# Radio.net
KiCad netlist of a schematic drawn in Altium Designer
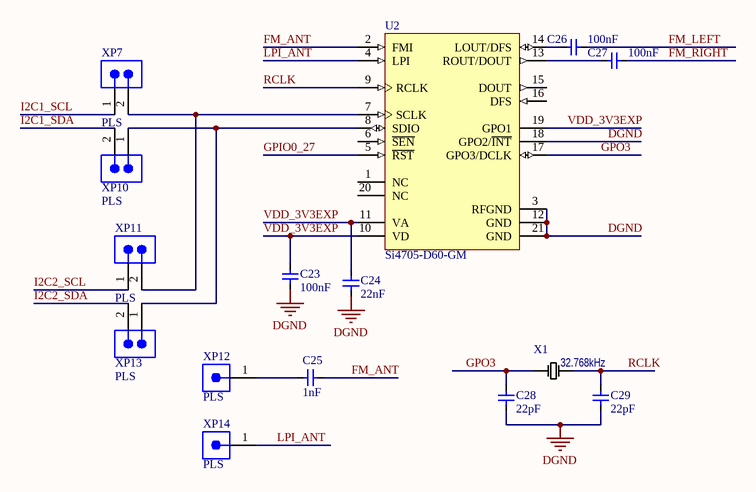
[diagram p0: Radio.SchDoc]

(export (version "E")
  (design (tool "Eeschema 10.0.6"))
  (components
    (comp (ref "C23")
      (value "100nF")
      (footprint "CAP0603R")
      (description "SMD 0805 Capacitor")
      (fields
        (field (name "PART NUMBER") "CC0603_100NF_50V_10%_X7R")
        (field (name "VOLTAGE") "50V")
        (field (name "AUTHOR") "I. Kuznetsov")
      )
      (libsource (lib "Capacitor") (part "CAP_NON_POLAR"))
    )
    (comp (ref "C24")
      (value "22nF")
      (footprint "CAP0603R")
      (description "SMD 0805 Capacitor")
      (fields
        (field (name "PART NUMBER") "CC0603_22NF_50V_10%_X7R")
        (field (name "VOLTAGE") "50V")
        (field (name "AUTHOR") "I. Kuznetsov")
      )
      (libsource (lib "Capacitor") (part "CAP_NON_POLAR"))
    )
    (comp (ref "C25")
      (value "1nF")
      (footprint "CAP0603R")
      (description "SMD 0805 Capacitor")
      (fields
        (field (name "PART NUMBER") "CC0603_1NF_50V_10%_X7R")
        (field (name "VOLTAGE") "50V")
        (field (name "AUTHOR") "I. Kuznetsov")
      )
      (libsource (lib "Capacitor") (part "CAP_NON_POLAR"))
    )
    (comp (ref "C26")
      (value "100nF")
      (footprint "CAP0603R")
      (description "SMD 0805 Capacitor")
      (fields
        (field (name "PART NUMBER") "CC0603_100NF_50V_10%_X7R")
        (field (name "VOLTAGE") "50V")
        (field (name "AUTHOR") "I. Kuznetsov")
      )
      (libsource (lib "Capacitor") (part "CAP_NON_POLAR"))
    )
    (comp (ref "C27")
      (value "100nF")
      (footprint "CAP0603R")
      (description "SMD 0805 Capacitor")
      (fields
        (field (name "PART NUMBER") "CC0603_100NF_50V_10%_X7R")
        (field (name "VOLTAGE") "50V")
        (field (name "AUTHOR") "I. Kuznetsov")
      )
      (libsource (lib "Capacitor") (part "CAP_NON_POLAR"))
    )
    (comp (ref "C28")
      (value "22pF")
      (footprint "CAP0603R")
      (description "SMD 0805 Capacitor")
      (fields
        (field (name "PART NUMBER") "CC0603_22PF_50V_5%_NP0")
        (field (name "VOLTAGE") "50V")
        (field (name "AUTHOR") "I. Kuznetsov")
      )
      (libsource (lib "Capacitor") (part "CAP_NON_POLAR"))
    )
    (comp (ref "C29")
      (value "22pF")
      (footprint "CAP0603R")
      (description "SMD 0805 Capacitor")
      (fields
        (field (name "PART NUMBER") "CC0603_22PF_50V_5%_NP0")
        (field (name "VOLTAGE") "50V")
        (field (name "AUTHOR") "I. Kuznetsov")
      )
      (libsource (lib "Capacitor") (part "CAP_NON_POLAR"))
    )
    (comp (ref "U2")
      (value "Si4705-D60-GM")
      (footprint "SLAB-QFN-20-1700x1700TP_V")
      (description "Broadcast FM Radio Receiver with RDS / RBDS, -20 to 85 degC, 20-pin QFN, Tray")
      (fields (field (name "MANUFACTURER") "Silicon Labs"))
      (libsource (lib "Altium Content Vault") (part "SLAB-Si4704_4705-QFN-20-21"))
    )
    (comp (ref "X1")
      (value "32.768kHz")
      (footprint "5020")
      (description "Кварцевый резонатор")
      (fields (field (name "PART NUMBER") "CC4V-T1A") (field (name "AUTHOR") "I. Kuznetsov"))
      (libsource (lib "Crystall") (part "2_PIN_XTAL"))
    )
    (comp (ref "XP7")
      (value "PLS")
      (footprint "PLS-02")
      (fields (field (name "PART NUMBER") "PLS-02") (field (name "MANUFACTURER") "AUK"))
      (libsource (lib "Connector") (part "CN_02P_1W"))
    )
    (comp (ref "XP10")
      (value "PLS")
      (footprint "PLS-02")
      (fields (field (name "PART NUMBER") "PLS-02") (field (name "MANUFACTURER") "AUK"))
      (libsource (lib "") (part "CN_02P_1W_1"))
    )
    (comp (ref "XP11")
      (value "PLS")
      (footprint "PLS-02")
      (fields (field (name "PART NUMBER") "PLS-02") (field (name "MANUFACTURER") "AUK"))
      (libsource (lib "Connector") (part "CN_02P_1W"))
    )
    (comp (ref "XP12")
      (value "PLS")
      (footprint "PLS-01")
      (fields (field (name "PART NUMBER") "PLS-01") (field (name "MANUFACTURER") "AUK"))
      (libsource (lib "Connector") (part "CN_01P_1W"))
    )
    (comp (ref "XP13")
      (value "PLS")
      (footprint "PLS-02")
      (fields (field (name "PART NUMBER") "PLS-02") (field (name "MANUFACTURER") "AUK"))
      (libsource (lib "") (part "CN_02P_1W_1"))
    )
    (comp (ref "XP14")
      (value "PLS")
      (footprint "PLS-01")
      (fields (field (name "PART NUMBER") "PLS-01") (field (name "MANUFACTURER") "AUK"))
      (libsource (lib "Connector") (part "CN_01P_1W"))
    )
  )
  (nets
    (net (code "1") (name "/FM_ANT") (class "Default")
      (node (ref "C25") (pin "2") (pinfunction "2_2") (pintype "passive"))
      (node (ref "U2") (pin "2") (pinfunction "FMI_2") (pintype "input"))
    )
    (net (code "2") (name "/FM_LEFT") (class "Default")
      (node (ref "C26") (pin "1") (pinfunction "1_1") (pintype "passive"))
    )
    (net (code "3") (name "/FM_RIGHT") (class "Default")
      (node (ref "C27") (pin "1") (pinfunction "1_1") (pintype "passive"))
    )
    (net (code "4") (name "/GPIO0_27") (class "Default")
      (node (ref "U2") (pin "5") (pinfunction "~{RST}_5") (pintype "input"))
    )
    (net (code "5") (name "/GPO3") (class "Default")
      (node (ref "C28") (pin "2") (pinfunction "2_2") (pintype "passive"))
      (node (ref "U2") (pin "17") (pinfunction "GPO3/DCLK_17") (pintype "bidirectional"))
      (node (ref "X1") (pin "1") (pinfunction "1_1") (pintype "passive"))
    )
    (net (code "6") (name "/I2C1_SCL") (class "Default")
      (node (ref "XP7") (pin "1") (pinfunction "1_1") (pintype "passive"))
    )
    (net (code "7") (name "/I2C1_SDA") (class "Default")
      (node (ref "XP10") (pin "2") (pinfunction "2_2") (pintype "passive"))
    )
    (net (code "8") (name "/I2C2_SCL") (class "Default")
      (node (ref "XP11") (pin "1") (pinfunction "1_1") (pintype "passive"))
    )
    (net (code "9") (name "/I2C2_SDA") (class "Default")
      (node (ref "XP13") (pin "2") (pinfunction "2_2") (pintype "passive"))
    )
    (net (code "10") (name "/LPI_ANT") (class "Default")
      (node (ref "U2") (pin "4") (pinfunction "LPI_4") (pintype "input"))
      (node (ref "XP14") (pin "1") (pinfunction "1_1") (pintype "passive"))
    )
    (net (code "11") (name "/RCLK") (class "Default")
      (node (ref "C29") (pin "2") (pinfunction "2_2") (pintype "passive"))
      (node (ref "U2") (pin "9") (pinfunction "RCLK_9") (pintype "input"))
      (node (ref "X1") (pin "2") (pinfunction "2_2") (pintype "passive"))
    )
    (net (code "12") (name "/VDD_3V3EXP") (class "Default")
      (node (ref "C23") (pin "2") (pinfunction "2_2") (pintype "passive"))
      (node (ref "C24") (pin "1") (pinfunction "1_1") (pintype "passive"))
      (node (ref "U2") (pin "10") (pinfunction "VD_10") (pintype "power_in"))
      (node (ref "U2") (pin "11") (pinfunction "VA_11") (pintype "power_in"))
      (node (ref "U2") (pin "19") (pinfunction "GPO1_19") (pintype "tri_state"))
    )
    (net (code "13") (name "DGND") (class "Default")
      (node (ref "C23") (pin "1") (pinfunction "1_1") (pintype "passive"))
      (node (ref "C24") (pin "2") (pinfunction "2_2") (pintype "passive"))
      (node (ref "C28") (pin "1") (pinfunction "1_1") (pintype "passive"))
      (node (ref "C29") (pin "1") (pinfunction "1_1") (pintype "passive"))
      (node (ref "U2") (pin "12") (pinfunction "GND_12") (pintype "power_in"))
      (node (ref "U2") (pin "18") (pinfunction "GPO2/~{INT}_18") (pintype "tri_state"))
      (node (ref "U2") (pin "21") (pinfunction "GND_21") (pintype "power_in"))
      (node (ref "U2") (pin "3") (pinfunction "RFGND_3") (pintype "power_in"))
    )
    (net (code "14") (name "Net-(C25-Pad1)") (class "Default")
      (node (ref "C25") (pin "1") (pinfunction "1_1") (pintype "passive"))
      (node (ref "XP12") (pin "1") (pinfunction "1_1") (pintype "passive"))
    )
    (net (code "15") (name "Net-(U2-LOUT{slash}DFS)") (class "Default")
      (node (ref "C26") (pin "2") (pinfunction "2_2") (pintype "passive"))
      (node (ref "U2") (pin "14") (pinfunction "LOUT/DFS_14") (pintype "bidirectional"))
    )
    (net (code "16") (name "Net-(U2-ROUT{slash}DOUT)") (class "Default")
      (node (ref "C27") (pin "2") (pinfunction "2_2") (pintype "passive"))
      (node (ref "U2") (pin "13") (pinfunction "ROUT/DOUT_13") (pintype "output"))
    )
    (net (code "17") (name "Net-(U2-SCLK)") (class "Default")
      (node (ref "U2") (pin "7") (pinfunction "SCLK_7") (pintype "input"))
      (node (ref "XP11") (pin "2") (pinfunction "2_2") (pintype "passive"))
      (node (ref "XP7") (pin "2") (pinfunction "2_2") (pintype "passive"))
    )
    (net (code "18") (name "Net-(U2-SDIO)") (class "Default")
      (node (ref "U2") (pin "8") (pinfunction "SDIO_8") (pintype "bidirectional"))
      (node (ref "XP10") (pin "1") (pinfunction "1_1") (pintype "passive"))
      (node (ref "XP13") (pin "1") (pinfunction "1_1") (pintype "passive"))
    )
    (net (code "19") (name "unconnected-(U2-DFS-Pad16)") (class "Default")
      (node (ref "U2") (pin "16") (pinfunction "DFS_16") (pintype "input"))
    )
    (net (code "20") (name "unconnected-(U2-DOUT-Pad15)") (class "Default")
      (node (ref "U2") (pin "15") (pinfunction "DOUT_15") (pintype "output"))
    )
    (net (code "21") (name "unconnected-(U2-NC-Pad1)") (class "Default")
      (node (ref "U2") (pin "1") (pinfunction "NC_1") (pintype "passive"))
    )
    (net (code "22") (name "unconnected-(U2-NC-Pad20)") (class "Default")
      (node (ref "U2") (pin "20") (pinfunction "NC_20") (pintype "passive"))
    )
    (net (code "23") (name "unconnected-(U2-~{SEN}-Pad6)") (class "Default")
      (node (ref "U2") (pin "6") (pinfunction "~{SEN}_6") (pintype "input"))
    )
  )
)
